# cpuadcinput.net
KiCad netlist of a schematic drawn in Altium Designer
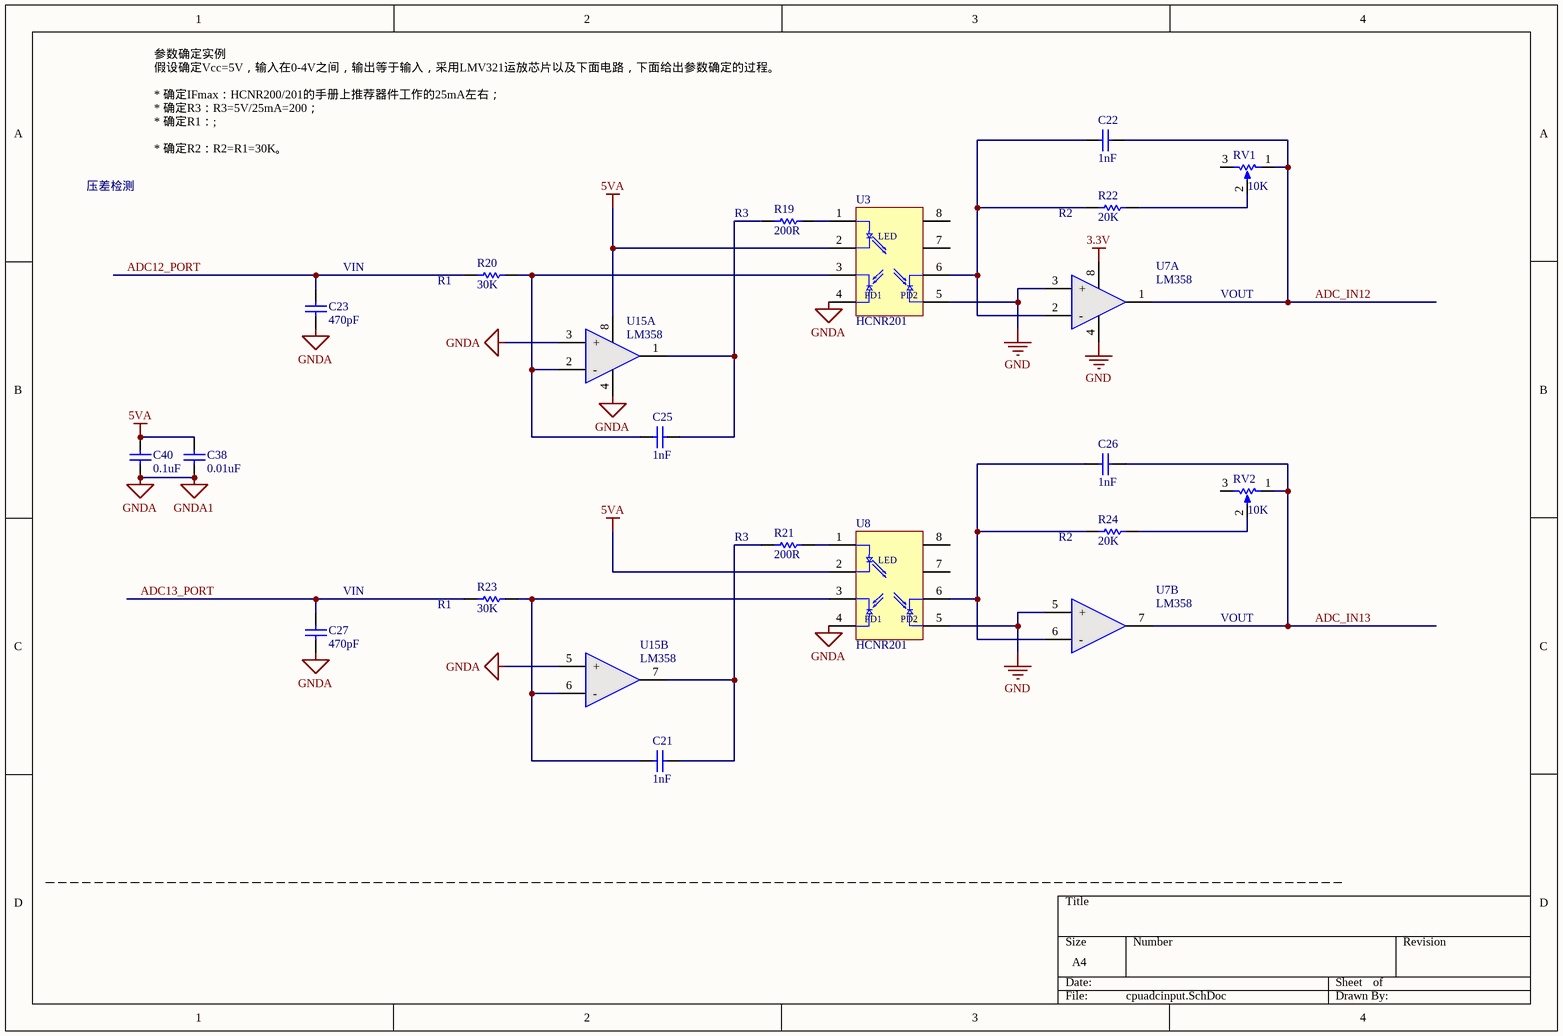
[diagram p0: cpuadcinput.SchDoc]

(export (version "E")
  (design (tool "Eeschema 10.0.6"))
  (components
    (comp (ref "C21")
      (value "1nF")
      (footprint "CAPC2012M")
      (description "Capacitor")
      (fields (field (name "PUBLISHER") "Altium Limited"))
      (libsource (lib "Miscellaneous Devices") (part "Cap"))
    )
    (comp (ref "C22")
      (value "1nF")
      (footprint "CAPC2012M")
      (description "Capacitor")
      (fields (field (name "PUBLISHER") "Altium Limited"))
      (libsource (lib "Miscellaneous Devices") (part "Cap"))
    )
    (comp (ref "C23")
      (value "470pF")
      (footprint "CAPC2012M")
      (description "Capacitor")
      (fields (field (name "PUBLISHER") "Altium Limited"))
      (libsource (lib "Miscellaneous Devices") (part "Cap"))
    )
    (comp (ref "C25")
      (value "1nF")
      (footprint "CAPC2012M")
      (description "Capacitor")
      (fields (field (name "PUBLISHER") "Altium Limited"))
      (libsource (lib "Miscellaneous Devices") (part "Cap"))
    )
    (comp (ref "C26")
      (value "1nF")
      (footprint "CAPC2012M")
      (description "Capacitor")
      (fields (field (name "PUBLISHER") "Altium Limited"))
      (libsource (lib "Miscellaneous Devices") (part "Cap"))
    )
    (comp (ref "C27")
      (value "470pF")
      (footprint "CAPC2012M")
      (description "Capacitor")
      (fields (field (name "PUBLISHER") "Altium Limited"))
      (libsource (lib "Miscellaneous Devices") (part "Cap"))
    )
    (comp (ref "C38")
      (value "0.01uF")
      (footprint "CAPC2012M")
      (description "Capacitor")
      (fields (field (name "PUBLISHER") "Altium Limited"))
      (libsource (lib "Miscellaneous Devices") (part "Cap"))
    )
    (comp (ref "C40")
      (value "0.1uF")
      (footprint "CAPC2012M")
      (description "Capacitor")
      (fields (field (name "PUBLISHER") "Altium Limited"))
      (libsource (lib "Miscellaneous Devices") (part "Cap"))
    )
    (comp (ref "R19")
      (value "200R")
      (footprint "RESC2012M")
      (description "Resistor")
      (fields (field (name "PUBLISHER") "Altium Limited"))
      (libsource (lib "Miscellaneous Devices") (part "Res1"))
    )
    (comp (ref "R20")
      (value "30K")
      (footprint "RESC2012M")
      (description "Resistor")
      (fields (field (name "PUBLISHER") "Altium Limited"))
      (libsource (lib "Miscellaneous Devices") (part "Res1"))
    )
    (comp (ref "R21")
      (value "200R")
      (footprint "RESC2012M")
      (description "Resistor")
      (fields (field (name "PUBLISHER") "Altium Limited"))
      (libsource (lib "Miscellaneous Devices") (part "Res1"))
    )
    (comp (ref "R22")
      (value "20K")
      (footprint "RESC2012M")
      (description "Resistor")
      (fields (field (name "PUBLISHER") "Altium Limited"))
      (libsource (lib "Miscellaneous Devices") (part "Res1"))
    )
    (comp (ref "R23")
      (value "30K")
      (footprint "RESC2012M")
      (description "Resistor")
      (fields (field (name "PUBLISHER") "Altium Limited"))
      (libsource (lib "Miscellaneous Devices") (part "Res1"))
    )
    (comp (ref "R24")
      (value "20K")
      (footprint "RESC2012M")
      (description "Resistor")
      (fields (field (name "PUBLISHER") "Altium Limited"))
      (libsource (lib "Miscellaneous Devices") (part "Res1"))
    )
    (comp (ref "RV1")
      (value "10K")
      (footprint "3224W")
      (description "Potentiometer")
      (fields (field (name "PUBLISHER") "Altium Limited"))
      (libsource (lib "UserLib") (part "RPot-A"))
    )
    (comp (ref "RV2")
      (value "10K")
      (footprint "3224W")
      (description "Potentiometer")
      (fields (field (name "PUBLISHER") "Altium Limited"))
      (libsource (lib "UserLib") (part "RPot-A"))
    )
    (comp (ref "U3")
      (value "HCNR201")
      (footprint "SO8WL")
      (description "High-Linearity Analog  Optocouplers")
      (libsource (lib "UserSchDev") (part "HCNR200/201"))
    )
    (comp (ref "U7")
      (value "LM358")
      (footprint "NSO8_N")
      (description "双运放")
      (libsource (lib "UserSchDev") (part "LM358"))
    )
    (comp (ref "U8")
      (value "HCNR201")
      (footprint "SO8WL")
      (description "High-Linearity Analog  Optocouplers")
      (libsource (lib "UserSchDev") (part "HCNR200/201"))
    )
    (comp (ref "U15")
      (value "LM358")
      (footprint "NSO8_N")
      (description "双运放")
      (libsource (lib "UserSchDev") (part "LM358"))
    )
  )
  (nets
    (net (code "1") (name "/ADC12_PORT") (class "Default")
      (node (ref "C23") (pin "2") (pinfunction "2_2") (pintype "passive"))
      (node (ref "R20") (pin "2") (pinfunction "2_2") (pintype "passive"))
    )
    (net (code "2") (name "/ADC13_PORT") (class "Default")
      (node (ref "C27") (pin "2") (pinfunction "2_2") (pintype "passive"))
      (node (ref "R23") (pin "2") (pinfunction "2_2") (pintype "passive"))
    )
    (net (code "3") (name "/ADC_IN12") (class "Default")
      (node (ref "C22") (pin "2") (pinfunction "2_2") (pintype "passive"))
      (node (ref "RV1") (pin "1") (pinfunction "TOP_1") (pintype "passive"))
      (node (ref "U7") (pin "1") (pinfunction "OUT1_1") (pintype "passive"))
    )
    (net (code "4") (name "/ADC_IN13") (class "Default")
      (node (ref "C26") (pin "2") (pinfunction "2_2") (pintype "passive"))
      (node (ref "RV2") (pin "1") (pinfunction "TOP_1") (pintype "passive"))
      (node (ref "U7") (pin "7") (pinfunction "OUT2_7") (pintype "passive"))
    )
    (net (code "5") (name "3.3V") (class "Default")
      (node (ref "U7") (pin "8") (pinfunction "V+_8") (pintype "power_in"))
    )
    (net (code "6") (name "5VA") (class "Default")
      (node (ref "C38") (pin "2") (pinfunction "2_2") (pintype "passive"))
      (node (ref "C40") (pin "2") (pinfunction "2_2") (pintype "passive"))
      (node (ref "U15") (pin "8") (pinfunction "V+_8") (pintype "power_in"))
      (node (ref "U3") (pin "2") (pinfunction "ANODE_2") (pintype "passive"))
      (node (ref "U8") (pin "2") (pinfunction "ANODE_2") (pintype "passive"))
    )
    (net (code "7") (name "GND") (class "Default")
      (node (ref "U3") (pin "5") (pinfunction "GND_5") (pintype "passive"))
      (node (ref "U7") (pin "3") (pinfunction "+_3") (pintype "passive"))
      (node (ref "U7") (pin "4") (pinfunction "V-_4") (pintype "power_in"))
      (node (ref "U7") (pin "5") (pinfunction "+_5") (pintype "passive"))
      (node (ref "U8") (pin "5") (pinfunction "GND_5") (pintype "passive"))
    )
    (net (code "8") (name "GNDA") (class "Default")
      (node (ref "C23") (pin "1") (pinfunction "1_1") (pintype "passive"))
      (node (ref "C27") (pin "1") (pinfunction "1_1") (pintype "passive"))
      (node (ref "C38") (pin "1") (pinfunction "1_1") (pintype "passive"))
      (node (ref "C40") (pin "1") (pinfunction "1_1") (pintype "passive"))
      (node (ref "U15") (pin "3") (pinfunction "+_3") (pintype "passive"))
      (node (ref "U15") (pin "4") (pinfunction "V-_4") (pintype "power_in"))
      (node (ref "U15") (pin "5") (pinfunction "+_5") (pintype "passive"))
      (node (ref "U3") (pin "4") (pinfunction "NC_4") (pintype "passive"))
      (node (ref "U8") (pin "4") (pinfunction "NC_4") (pintype "passive"))
    )
    (net (code "9") (name "Net-(R19-Pad2)") (class "Default")
      (node (ref "R19") (pin "2") (pinfunction "2_2") (pintype "passive"))
      (node (ref "U3") (pin "1") (pinfunction "NC_1") (pintype "power_in"))
    )
    (net (code "10") (name "Net-(R21-Pad2)") (class "Default")
      (node (ref "R21") (pin "2") (pinfunction "2_2") (pintype "passive"))
      (node (ref "U8") (pin "1") (pinfunction "NC_1") (pintype "power_in"))
    )
    (net (code "11") (name "Net-(RV1-TAP)") (class "Default")
      (node (ref "R22") (pin "1") (pinfunction "1_1") (pintype "passive"))
      (node (ref "RV1") (pin "2") (pinfunction "TAP_2") (pintype "passive"))
    )
    (net (code "12") (name "Net-(RV2-TAP)") (class "Default")
      (node (ref "R24") (pin "1") (pinfunction "1_1") (pintype "passive"))
      (node (ref "RV2") (pin "2") (pinfunction "TAP_2") (pintype "passive"))
    )
    (net (code "13") (name "Net-(U3-Vo)") (class "Default")
      (node (ref "C22") (pin "1") (pinfunction "1_1") (pintype "passive"))
      (node (ref "R22") (pin "2") (pinfunction "2_2") (pintype "passive"))
      (node (ref "U3") (pin "6") (pinfunction "Vo_6") (pintype "passive"))
      (node (ref "U7") (pin "2") (pinfunction "-_2") (pintype "passive"))
    )
    (net (code "14") (name "Net-(U7B--)") (class "Default")
      (node (ref "C26") (pin "1") (pinfunction "1_1") (pintype "passive"))
      (node (ref "R24") (pin "2") (pinfunction "2_2") (pintype "passive"))
      (node (ref "U7") (pin "6") (pinfunction "-_6") (pintype "passive"))
      (node (ref "U8") (pin "6") (pinfunction "Vo_6") (pintype "passive"))
    )
    (net (code "15") (name "Net-(U15A--)") (class "Default")
      (node (ref "C25") (pin "1") (pinfunction "1_1") (pintype "passive"))
      (node (ref "R20") (pin "1") (pinfunction "1_1") (pintype "passive"))
      (node (ref "U15") (pin "2") (pinfunction "-_2") (pintype "passive"))
      (node (ref "U3") (pin "3") (pinfunction "CATHODE_3") (pintype "passive"))
    )
    (net (code "16") (name "Net-(U15A-OUT1)") (class "Default")
      (node (ref "C25") (pin "2") (pinfunction "2_2") (pintype "passive"))
      (node (ref "R19") (pin "1") (pinfunction "1_1") (pintype "passive"))
      (node (ref "U15") (pin "1") (pinfunction "OUT1_1") (pintype "passive"))
    )
    (net (code "17") (name "Net-(U15B--)") (class "Default")
      (node (ref "C21") (pin "1") (pinfunction "1_1") (pintype "passive"))
      (node (ref "R23") (pin "1") (pinfunction "1_1") (pintype "passive"))
      (node (ref "U15") (pin "6") (pinfunction "-_6") (pintype "passive"))
      (node (ref "U8") (pin "3") (pinfunction "CATHODE_3") (pintype "passive"))
    )
    (net (code "18") (name "Net-(U15B-OUT2)") (class "Default")
      (node (ref "C21") (pin "2") (pinfunction "2_2") (pintype "passive"))
      (node (ref "R21") (pin "1") (pinfunction "1_1") (pintype "passive"))
      (node (ref "U15") (pin "7") (pinfunction "OUT2_7") (pintype "passive"))
    )
    (net (code "19") (name "unconnected-(RV1-BOT-Pad3)") (class "Default")
      (node (ref "RV1") (pin "3") (pinfunction "BOT_3") (pintype "passive"))
    )
    (net (code "20") (name "unconnected-(RV2-BOT-Pad3)") (class "Default")
      (node (ref "RV2") (pin "3") (pinfunction "BOT_3") (pintype "passive"))
    )
    (net (code "21") (name "unconnected-(U3-VCC-Pad8)") (class "Default")
      (node (ref "U3") (pin "8") (pinfunction "VCC_8") (pintype "power_in"))
    )
    (net (code "22") (name "unconnected-(U3-VL-Pad7)") (class "Default")
      (node (ref "U3") (pin "7") (pinfunction "VL_7") (pintype "passive"))
    )
    (net (code "23") (name "unconnected-(U8-VCC-Pad8)") (class "Default")
      (node (ref "U8") (pin "8") (pinfunction "VCC_8") (pintype "power_in"))
    )
    (net (code "24") (name "unconnected-(U8-VL-Pad7)") (class "Default")
      (node (ref "U8") (pin "7") (pinfunction "VL_7") (pintype "passive"))
    )
  )
)
